# mikrokontroler.net
KiCad netlist of a schematic drawn in Altium Designer
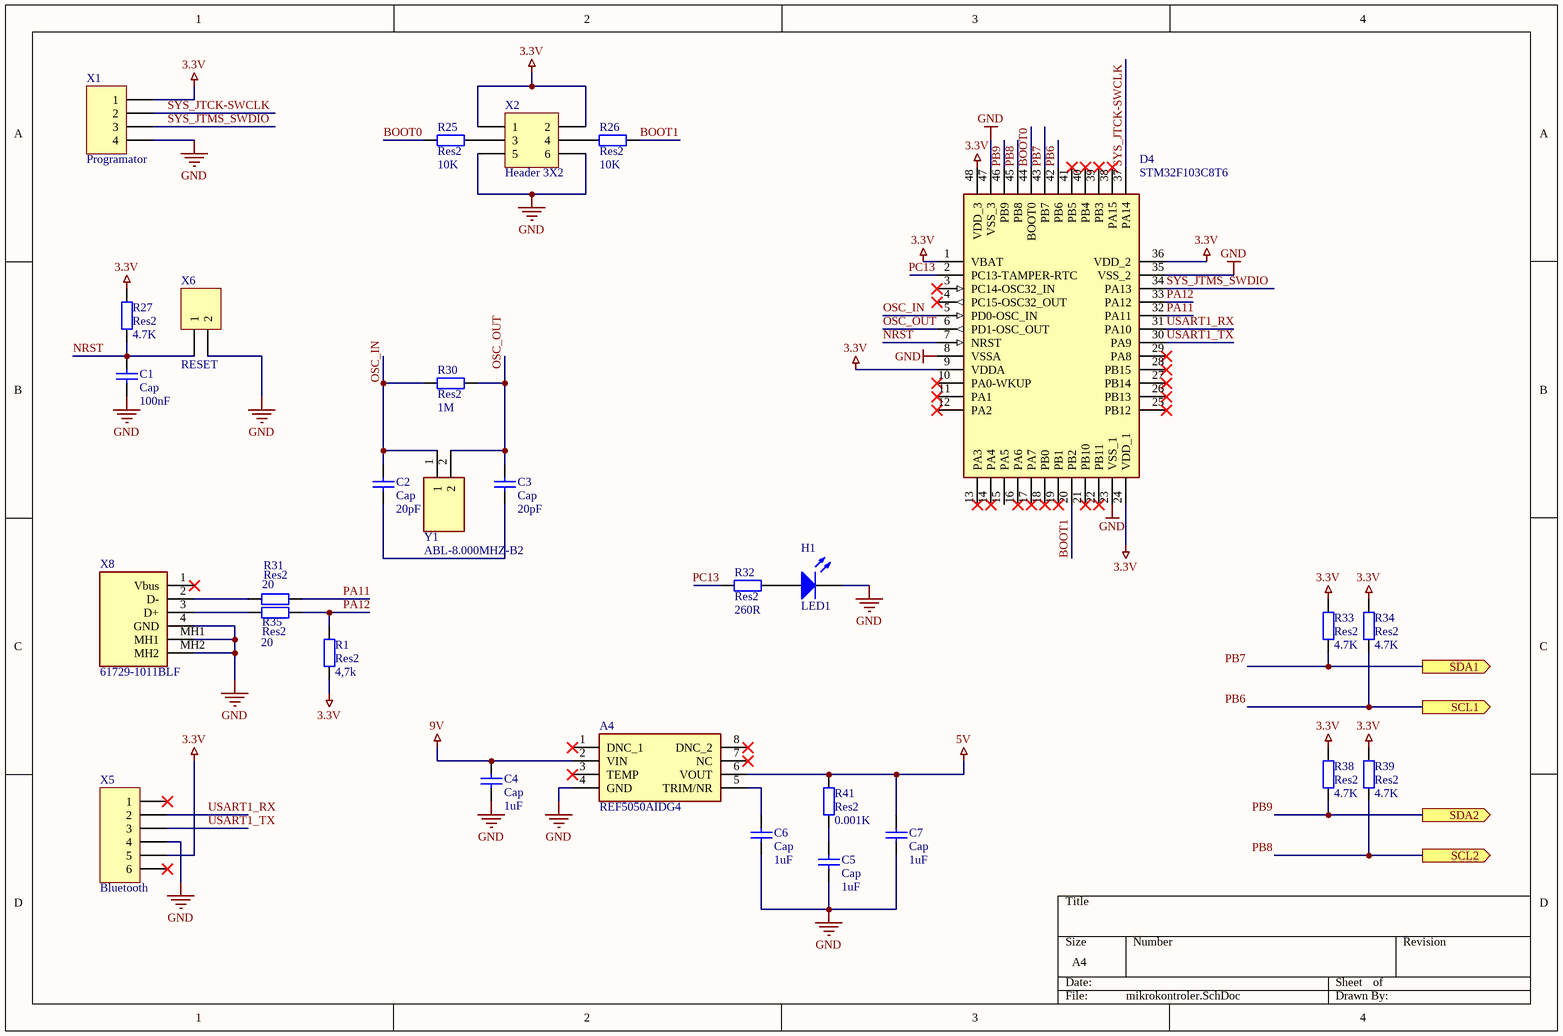
[diagram p0: mikrokontroler.SchDoc]

(export (version "E")
  (design (tool "Eeschema 10.0.6"))
  (components
    (comp (ref "A4")
      (value "REF5050AIDG4")
      (footprint "SamacSys:SOIC127P600X175-8N")
      (description "Integrated Circuit")
      (fields (field (name "MOUSER PART NUMBER") "595-REF5050AIDG4"))
      (libsource (lib "*") (part "REF5050AIDG4"))
    )
    (comp (ref "C1")
      (value "Cap")
      (footprint "6-0805_L")
      (description "Capacitor")
      (fields (field (name "ALTIUM_VALUE") "100nF") (field (name "PUBLISHER") "Altium Limited"))
      (libsource (lib "Miscellaneous Devices") (part "Cap"))
    )
    (comp (ref "C2")
      (value "Cap")
      (footprint "6-0805_L")
      (description "Capacitor")
      (fields (field (name "ALTIUM_VALUE") "20pF") (field (name "PUBLISHER") "Altium Limited"))
      (libsource (lib "Miscellaneous Devices") (part "Cap"))
    )
    (comp (ref "C3")
      (value "Cap")
      (footprint "6-0805_L")
      (description "Capacitor")
      (fields (field (name "ALTIUM_VALUE") "20pF") (field (name "PUBLISHER") "Altium Limited"))
      (libsource (lib "Miscellaneous Devices") (part "Cap"))
    )
    (comp (ref "C4")
      (value "Cap")
      (footprint "6-0805_L")
      (description "Capacitor")
      (fields (field (name "ALTIUM_VALUE") "1uF") (field (name "PUBLISHER") "Altium Limited"))
      (libsource (lib "Miscellaneous Devices") (part "Cap"))
    )
    (comp (ref "C5")
      (value "Cap")
      (footprint "6-0805_L")
      (description "Capacitor")
      (fields (field (name "ALTIUM_VALUE") "1uF") (field (name "PUBLISHER") "Altium Limited"))
      (libsource (lib "Miscellaneous Devices") (part "Cap"))
    )
    (comp (ref "C6")
      (value "Cap")
      (footprint "6-0805_L")
      (description "Capacitor")
      (fields (field (name "ALTIUM_VALUE") "1uF") (field (name "PUBLISHER") "Altium Limited"))
      (libsource (lib "Miscellaneous Devices") (part "Cap"))
    )
    (comp (ref "C7")
      (value "Cap")
      (footprint "6-0805_L")
      (description "Capacitor")
      (fields (field (name "ALTIUM_VALUE") "1uF") (field (name "PUBLISHER") "Altium Limited"))
      (libsource (lib "Miscellaneous Devices") (part "Cap"))
    )
    (comp (ref "D4")
      (value "STM32F103C8T6")
      (footprint "QFP50P900X900X160-48N")
      (description "Integrated Circuit")
      (fields
        (field (name "MOUSER PART NUMBER") "511-STM32F103C8T6")
        (field (name "RS PART NUMBER") "0402279P")
      )
      (libsource (lib "*") (part "STM32F103C8T6"))
    )
    (comp (ref "H1")
      (value "LED1")
      (footprint "LED-1")
      (description "Typical RED GaAs LED")
      (fields (field (name "PUBLISHER") "Altium Limited"))
      (libsource (lib "Miscellaneous Devices") (part "LED1"))
    )
    (comp (ref "R1")
      (value "Res2")
      (footprint "6-0805_L")
      (description "Resistor")
      (fields (field (name "ALTIUM_VALUE") "4,7k") (field (name "PUBLISHER") "Altium Limited"))
      (libsource (lib "") (part "Res2_1"))
    )
    (comp (ref "R25")
      (value "Res2")
      (footprint "6-0805_L")
      (description "Resistor")
      (fields (field (name "ALTIUM_VALUE") "10K") (field (name "PUBLISHER") "Altium Limited"))
      (libsource (lib "") (part "Res2_2"))
    )
    (comp (ref "R26")
      (value "Res2")
      (footprint "6-0805_L")
      (description "Resistor")
      (fields (field (name "ALTIUM_VALUE") "10K") (field (name "PUBLISHER") "Altium Limited"))
      (libsource (lib "") (part "Res2_2"))
    )
    (comp (ref "R27")
      (value "Res2")
      (footprint "6-0805_L")
      (description "Resistor")
      (fields (field (name "ALTIUM_VALUE") "4.7K") (field (name "PUBLISHER") "Altium Limited"))
      (libsource (lib "Miscellaneous Devices") (part "Res2"))
    )
    (comp (ref "R30")
      (value "Res2")
      (footprint "6-0805_L")
      (description "Resistor")
      (fields (field (name "ALTIUM_VALUE") "1M") (field (name "PUBLISHER") "Altium Limited"))
      (libsource (lib "") (part "Res2_2"))
    )
    (comp (ref "R31")
      (value "Res2")
      (footprint "6-0805_L")
      (description "Resistor")
      (fields (field (name "ALTIUM_VALUE") "20") (field (name "PUBLISHER") "Altium Limited"))
      (libsource (lib "") (part "Res2_2"))
    )
    (comp (ref "R32")
      (value "Res2")
      (footprint "6-0805_L")
      (description "Resistor")
      (fields (field (name "ALTIUM_VALUE") "260R") (field (name "PUBLISHER") "Altium Limited"))
      (libsource (lib "") (part "Res2_3"))
    )
    (comp (ref "R33")
      (value "Res2")
      (footprint "6-0805_L")
      (description "Resistor")
      (fields (field (name "ALTIUM_VALUE") "4.7K") (field (name "PUBLISHER") "Altium Limited"))
      (libsource (lib "Miscellaneous Devices") (part "Res2"))
    )
    (comp (ref "R34")
      (value "Res2")
      (footprint "6-0805_L")
      (description "Resistor")
      (fields (field (name "ALTIUM_VALUE") "4.7K") (field (name "PUBLISHER") "Altium Limited"))
      (libsource (lib "Miscellaneous Devices") (part "Res2"))
    )
    (comp (ref "R35")
      (value "Res2")
      (footprint "6-0805_L")
      (description "Resistor")
      (fields (field (name "ALTIUM_VALUE") "20") (field (name "PUBLISHER") "Altium Limited"))
      (libsource (lib "") (part "Res2_2"))
    )
    (comp (ref "R38")
      (value "Res2")
      (footprint "6-0805_L")
      (description "Resistor")
      (fields (field (name "ALTIUM_VALUE") "4.7K") (field (name "PUBLISHER") "Altium Limited"))
      (libsource (lib "Miscellaneous Devices") (part "Res2"))
    )
    (comp (ref "R39")
      (value "Res2")
      (footprint "6-0805_L")
      (description "Resistor")
      (fields (field (name "ALTIUM_VALUE") "4.7K") (field (name "PUBLISHER") "Altium Limited"))
      (libsource (lib "Miscellaneous Devices") (part "Res2"))
    )
    (comp (ref "R41")
      (value "Res2")
      (footprint "6-0805_L")
      (description "Resistor")
      (fields (field (name "ALTIUM_VALUE") "0.001K") (field (name "PUBLISHER") "Altium Limited"))
      (libsource (lib "") (part "Res2_1"))
    )
    (comp (ref "X1")
      (value "Programator")
      (footprint "HDR1X4")
      (description "Header, 4-Pin")
      (fields (field (name "PUBLISHER") "Altium Limited"))
      (libsource (lib "Miscellaneous Connectors") (part "Header 4"))
    )
    (comp (ref "X2")
      (value "Header 3X2")
      (footprint "HDR2X3")
      (description "Header, 3-Pin, Dual row")
      (fields (field (name "PUBLISHER") "Altium Limited"))
      (libsource (lib "Miscellaneous Connectors") (part "Header 3X2"))
    )
    (comp (ref "X5")
      (value "Bluetooth")
      (footprint "HDR1X6")
      (description "Header, 6-Pin")
      (fields (field (name "PUBLISHER") "Altium Limited"))
      (libsource (lib "Miscellaneous Connectors") (part "Header 6"))
    )
    (comp (ref "X6")
      (value "RESET")
      (footprint "HDR1X2")
      (description "Header, 2-Pin")
      (fields (field (name "PUBLISHER") "Altium Limited"))
      (libsource (lib "Miscellaneous Connectors") (part "Header 2"))
    )
    (comp (ref "X8")
      (value "61729-1011BLF")
      (footprint "SamacSys2:617291011BLF")
      (description "Connector")
      (fields
        (field (name "MOUSER PART NUMBER") "649-61729-1011BLF")
        (field (name "RS PART NUMBER") "7710041")
      )
      (libsource (lib "SamacSys2") (part "61729-1011BLF"))
    )
    (comp (ref "Y1")
      (value "ABL-8.000MHZ-B2")
      (footprint "SamacSys2:HC/49US_(AT49)PTH")
      (description "Crystal or Oscillator")
      (fields (field (name "MOUSER PART NUMBER") "815-ABL-8-B2") (field (name "RS PART NUMBER") "1710614"))
      (libsource (lib "*") (part "ABL-8.000MHZ-B2"))
    )
  )
  (nets
    (net (code "1") (name "/BOOT0") (class "Default")
      (node (ref "D4") (pin "44") (pinfunction "BOOT0_44") (pintype "passive"))
      (node (ref "R25") (pin "2") (pinfunction "2_2") (pintype "passive"))
    )
    (net (code "2") (name "/BOOT1") (class "Default")
      (node (ref "D4") (pin "20") (pinfunction "PB2_20") (pintype "passive"))
      (node (ref "R26") (pin "1") (pinfunction "1_1") (pintype "passive"))
    )
    (net (code "3") (name "/NRST") (class "Default")
      (node (ref "C1") (pin "2") (pinfunction "2_2") (pintype "passive"))
      (node (ref "D4") (pin "7") (pinfunction "NRST_7") (pintype "input"))
      (node (ref "R27") (pin "1") (pinfunction "1_1") (pintype "passive"))
      (node (ref "X6") (pin "1") (pinfunction "1_1") (pintype "passive"))
    )
    (net (code "4") (name "/OSC_IN") (class "Default")
      (node (ref "C2") (pin "2") (pinfunction "2_2") (pintype "passive"))
      (node (ref "D4") (pin "5") (pinfunction "PD0-OSC_IN_5") (pintype "input"))
      (node (ref "R30") (pin "2") (pinfunction "2_2") (pintype "passive"))
      (node (ref "Y1") (pin "1") (pinfunction "1_1") (pintype "passive"))
    )
    (net (code "5") (name "/OSC_OUT") (class "Default")
      (node (ref "C3") (pin "2") (pinfunction "2_2") (pintype "passive"))
      (node (ref "D4") (pin "6") (pinfunction "PD1-OSC_OUT_6") (pintype "output"))
      (node (ref "R30") (pin "1") (pinfunction "1_1") (pintype "passive"))
      (node (ref "Y1") (pin "2") (pinfunction "2_2") (pintype "passive"))
    )
    (net (code "6") (name "/PA11") (class "Default")
      (node (ref "D4") (pin "32") (pinfunction "PA11_32") (pintype "passive"))
      (node (ref "R31") (pin "1") (pinfunction "1_1") (pintype "passive"))
    )
    (net (code "7") (name "/PA12") (class "Default")
      (node (ref "D4") (pin "33") (pinfunction "PA12_33") (pintype "passive"))
      (node (ref "R1") (pin "1") (pinfunction "1_1") (pintype "passive"))
      (node (ref "R35") (pin "1") (pinfunction "1_1") (pintype "passive"))
    )
    (net (code "8") (name "/PB6") (class "Default")
      (node (ref "D4") (pin "42") (pinfunction "PB6_42") (pintype "passive"))
      (node (ref "R34") (pin "1") (pinfunction "1_1") (pintype "passive"))
    )
    (net (code "9") (name "/PB7") (class "Default")
      (node (ref "D4") (pin "43") (pinfunction "PB7_43") (pintype "passive"))
      (node (ref "R33") (pin "1") (pinfunction "1_1") (pintype "passive"))
    )
    (net (code "10") (name "/PB8") (class "Default")
      (node (ref "D4") (pin "45") (pinfunction "PB8_45") (pintype "passive"))
      (node (ref "R39") (pin "1") (pinfunction "1_1") (pintype "passive"))
    )
    (net (code "11") (name "/PB9") (class "Default")
      (node (ref "D4") (pin "46") (pinfunction "PB9_46") (pintype "passive"))
      (node (ref "R38") (pin "1") (pinfunction "1_1") (pintype "passive"))
    )
    (net (code "12") (name "/PC13") (class "Default")
      (node (ref "D4") (pin "2") (pinfunction "PC13-TAMPER-RTC_2") (pintype "passive"))
      (node (ref "R32") (pin "1") (pinfunction "1_1") (pintype "passive"))
    )
    (net (code "13") (name "/SYS_JTCK-SWCLK") (class "Default")
      (node (ref "D4") (pin "37") (pinfunction "PA14_37") (pintype "passive"))
      (node (ref "X1") (pin "2") (pinfunction "2_2") (pintype "passive"))
    )
    (net (code "14") (name "/SYS_JTMS_SWDIO") (class "Default")
      (node (ref "D4") (pin "34") (pinfunction "PA13_34") (pintype "passive"))
      (node (ref "X1") (pin "3") (pinfunction "3_3") (pintype "passive"))
    )
    (net (code "15") (name "/USART1_RX") (class "Default")
      (node (ref "D4") (pin "31") (pinfunction "PA10_31") (pintype "passive"))
      (node (ref "X5") (pin "2") (pinfunction "2_2") (pintype "passive"))
    )
    (net (code "16") (name "/USART1_TX") (class "Default")
      (node (ref "D4") (pin "30") (pinfunction "PA9_30") (pintype "passive"))
      (node (ref "X5") (pin "3") (pinfunction "3_3") (pintype "passive"))
    )
    (net (code "17") (name "3.3V") (class "Default")
      (node (ref "D4") (pin "1") (pinfunction "VBAT_1") (pintype "passive"))
      (node (ref "D4") (pin "24") (pinfunction "VDD_1_24") (pintype "power_in"))
      (node (ref "D4") (pin "36") (pinfunction "VDD_2_36") (pintype "power_in"))
      (node (ref "D4") (pin "48") (pinfunction "VDD_3_48") (pintype "power_in"))
      (node (ref "D4") (pin "9") (pinfunction "VDDA_9") (pintype "power_in"))
      (node (ref "R1") (pin "2") (pinfunction "2_2") (pintype "passive"))
      (node (ref "R27") (pin "2") (pinfunction "2_2") (pintype "passive"))
      (node (ref "R33") (pin "2") (pinfunction "2_2") (pintype "passive"))
      (node (ref "R34") (pin "2") (pinfunction "2_2") (pintype "passive"))
      (node (ref "R38") (pin "2") (pinfunction "2_2") (pintype "passive"))
      (node (ref "R39") (pin "2") (pinfunction "2_2") (pintype "passive"))
      (node (ref "X1") (pin "1") (pinfunction "1_1") (pintype "passive"))
      (node (ref "X2") (pin "1") (pinfunction "1_1") (pintype "passive"))
      (node (ref "X2") (pin "2") (pinfunction "2_2") (pintype "passive"))
      (node (ref "X5") (pin "5") (pinfunction "5_5") (pintype "passive"))
    )
    (net (code "18") (name "5V") (class "Default")
      (node (ref "A4") (pin "6") (pinfunction "VOUT_6") (pintype "passive"))
      (node (ref "C7") (pin "2") (pinfunction "2_2") (pintype "passive"))
      (node (ref "R41") (pin "1") (pinfunction "1_1") (pintype "passive"))
    )
    (net (code "19") (name "9V") (class "Default")
      (node (ref "A4") (pin "2") (pinfunction "VIN_2") (pintype "passive"))
      (node (ref "C4") (pin "2") (pinfunction "2_2") (pintype "passive"))
    )
    (net (code "20") (name "GND") (class "Default")
      (node (ref "A4") (pin "4") (pinfunction "GND_4") (pintype "passive"))
      (node (ref "C1") (pin "1") (pinfunction "1_1") (pintype "passive"))
      (node (ref "C4") (pin "1") (pinfunction "1_1") (pintype "passive"))
      (node (ref "C5") (pin "1") (pinfunction "1_1") (pintype "passive"))
      (node (ref "C6") (pin "1") (pinfunction "1_1") (pintype "passive"))
      (node (ref "C7") (pin "1") (pinfunction "1_1") (pintype "passive"))
      (node (ref "D4") (pin "23") (pinfunction "VSS_1_23") (pintype "power_in"))
      (node (ref "D4") (pin "35") (pinfunction "VSS_2_35") (pintype "power_in"))
      (node (ref "D4") (pin "47") (pinfunction "VSS_3_47") (pintype "power_in"))
      (node (ref "D4") (pin "8") (pinfunction "VSSA_8") (pintype "power_in"))
      (node (ref "H1") (pin "2") (pinfunction "K_2") (pintype "passive"))
      (node (ref "X1") (pin "4") (pinfunction "4_4") (pintype "passive"))
      (node (ref "X2") (pin "5") (pinfunction "5_5") (pintype "passive"))
      (node (ref "X2") (pin "6") (pinfunction "6_6") (pintype "passive"))
      (node (ref "X5") (pin "4") (pinfunction "4_4") (pintype "passive"))
      (node (ref "X6") (pin "2") (pinfunction "2_2") (pintype "passive"))
      (node (ref "X8") (pin "4") (pinfunction "GND_4") (pintype "passive"))
      (node (ref "X8") (pin "MH1") (pinfunction "MH1_MH1") (pintype "passive"))
      (node (ref "X8") (pin "MH2") (pinfunction "MH2_MH2") (pintype "passive"))
    )
    (net (code "21") (name "Net-(A4-TRIM{slash}NR)") (class "Default")
      (node (ref "A4") (pin "5") (pinfunction "TRIM/NR_5") (pintype "passive"))
      (node (ref "C6") (pin "2") (pinfunction "2_2") (pintype "passive"))
    )
    (net (code "22") (name "Net-(C2-Pad1)") (class "Default")
      (node (ref "C2") (pin "1") (pinfunction "1_1") (pintype "passive"))
      (node (ref "C3") (pin "1") (pinfunction "1_1") (pintype "passive"))
    )
    (net (code "23") (name "Net-(C5-Pad2)") (class "Default")
      (node (ref "C5") (pin "2") (pinfunction "2_2") (pintype "passive"))
      (node (ref "R41") (pin "2") (pinfunction "2_2") (pintype "passive"))
    )
    (net (code "24") (name "Net-(H1-A)") (class "Default")
      (node (ref "H1") (pin "1") (pinfunction "A_1") (pintype "passive"))
      (node (ref "R32") (pin "2") (pinfunction "2_2") (pintype "passive"))
    )
    (net (code "25") (name "Net-(R25-Pad1)") (class "Default")
      (node (ref "R25") (pin "1") (pinfunction "1_1") (pintype "passive"))
      (node (ref "X2") (pin "3") (pinfunction "3_3") (pintype "passive"))
    )
    (net (code "26") (name "Net-(R26-Pad2)") (class "Default")
      (node (ref "R26") (pin "2") (pinfunction "2_2") (pintype "passive"))
      (node (ref "X2") (pin "4") (pinfunction "4_4") (pintype "passive"))
    )
    (net (code "27") (name "Net-(X8-D+)") (class "Default")
      (node (ref "R35") (pin "2") (pinfunction "2_2") (pintype "passive"))
      (node (ref "X8") (pin "3") (pinfunction "D+_3") (pintype "passive"))
    )
    (net (code "28") (name "Net-(X8-D-)") (class "Default")
      (node (ref "R31") (pin "2") (pinfunction "2_2") (pintype "passive"))
      (node (ref "X8") (pin "2") (pinfunction "D-_2") (pintype "passive"))
    )
    (net (code "29") (name "unconnected-(A4-DNC_1-Pad1)") (class "Default")
      (node (ref "A4") (pin "1") (pinfunction "DNC_1_1") (pintype "passive+no_connect"))
    )
    (net (code "30") (name "unconnected-(A4-DNC_2-Pad8)") (class "Default")
      (node (ref "A4") (pin "8") (pinfunction "DNC_2_8") (pintype "passive+no_connect"))
    )
    (net (code "31") (name "unconnected-(A4-NC-Pad7)") (class "Default")
      (node (ref "A4") (pin "7") (pinfunction "NC_7") (pintype "passive+no_connect"))
    )
    (net (code "32") (name "unconnected-(A4-TEMP-Pad3)") (class "Default")
      (node (ref "A4") (pin "3") (pinfunction "TEMP_3") (pintype "passive+no_connect"))
    )
    (net (code "33") (name "unconnected-(D4-PA0-WKUP-Pad10)") (class "Default")
      (node (ref "D4") (pin "10") (pinfunction "PA0-WKUP_10") (pintype "passive+no_connect"))
    )
    (net (code "34") (name "unconnected-(D4-PA1-Pad11)") (class "Default")
      (node (ref "D4") (pin "11") (pinfunction "PA1_11") (pintype "passive+no_connect"))
    )
    (net (code "35") (name "unconnected-(D4-PA2-Pad12)") (class "Default")
      (node (ref "D4") (pin "12") (pinfunction "PA2_12") (pintype "passive+no_connect"))
    )
    (net (code "36") (name "unconnected-(D4-PA3-Pad13)") (class "Default")
      (node (ref "D4") (pin "13") (pinfunction "PA3_13") (pintype "passive+no_connect"))
    )
    (net (code "37") (name "unconnected-(D4-PA4-Pad14)") (class "Default")
      (node (ref "D4") (pin "14") (pinfunction "PA4_14") (pintype "passive+no_connect"))
    )
    (net (code "38") (name "unconnected-(D4-PA5-Pad15)") (class "Default")
      (node (ref "D4") (pin "15") (pinfunction "PA5_15") (pintype "passive"))
    )
    (net (code "39") (name "unconnected-(D4-PA6-Pad16)") (class "Default")
      (node (ref "D4") (pin "16") (pinfunction "PA6_16") (pintype "passive+no_connect"))
    )
    (net (code "40") (name "unconnected-(D4-PA7-Pad17)") (class "Default")
      (node (ref "D4") (pin "17") (pinfunction "PA7_17") (pintype "passive+no_connect"))
    )
    (net (code "41") (name "unconnected-(D4-PA8-Pad29)") (class "Default")
      (node (ref "D4") (pin "29") (pinfunction "PA8_29") (pintype "passive+no_connect"))
    )
    (net (code "42") (name "unconnected-(D4-PA15-Pad38)") (class "Default")
      (node (ref "D4") (pin "38") (pinfunction "PA15_38") (pintype "passive+no_connect"))
    )
    (net (code "43") (name "unconnected-(D4-PB0-Pad18)") (class "Default")
      (node (ref "D4") (pin "18") (pinfunction "PB0_18") (pintype "passive+no_connect"))
    )
    (net (code "44") (name "unconnected-(D4-PB1-Pad19)") (class "Default")
      (node (ref "D4") (pin "19") (pinfunction "PB1_19") (pintype "passive+no_connect"))
    )
    (net (code "45") (name "unconnected-(D4-PB3-Pad39)") (class "Default")
      (node (ref "D4") (pin "39") (pinfunction "PB3_39") (pintype "passive+no_connect"))
    )
    (net (code "46") (name "unconnected-(D4-PB4-Pad40)") (class "Default")
      (node (ref "D4") (pin "40") (pinfunction "PB4_40") (pintype "passive+no_connect"))
    )
    (net (code "47") (name "unconnected-(D4-PB5-Pad41)") (class "Default")
      (node (ref "D4") (pin "41") (pinfunction "PB5_41") (pintype "passive+no_connect"))
    )
    (net (code "48") (name "unconnected-(D4-PB10-Pad21)") (class "Default")
      (node (ref "D4") (pin "21") (pinfunction "PB10_21") (pintype "passive+no_connect"))
    )
    (net (code "49") (name "unconnected-(D4-PB11-Pad22)") (class "Default")
      (node (ref "D4") (pin "22") (pinfunction "PB11_22") (pintype "passive+no_connect"))
    )
    (net (code "50") (name "unconnected-(D4-PB12-Pad25)") (class "Default")
      (node (ref "D4") (pin "25") (pinfunction "PB12_25") (pintype "passive+no_connect"))
    )
    (net (code "51") (name "unconnected-(D4-PB13-Pad26)") (class "Default")
      (node (ref "D4") (pin "26") (pinfunction "PB13_26") (pintype "passive+no_connect"))
    )
    (net (code "52") (name "unconnected-(D4-PB14-Pad27)") (class "Default")
      (node (ref "D4") (pin "27") (pinfunction "PB14_27") (pintype "passive+no_connect"))
    )
    (net (code "53") (name "unconnected-(D4-PB15-Pad28)") (class "Default")
      (node (ref "D4") (pin "28") (pinfunction "PB15_28") (pintype "passive+no_connect"))
    )
    (net (code "54") (name "unconnected-(D4-PC14-OSC32_IN-Pad3)") (class "Default")
      (node (ref "D4") (pin "3") (pinfunction "PC14-OSC32_IN_3") (pintype "input+no_connect"))
    )
    (net (code "55") (name "unconnected-(D4-PC15-OSC32_OUT-Pad4)") (class "Default")
      (node (ref "D4") (pin "4") (pinfunction "PC15-OSC32_OUT_4") (pintype "output+no_connect"))
    )
    (net (code "56") (name "unconnected-(X5-Pad1)") (class "Default")
      (node (ref "X5") (pin "1") (pinfunction "1_1") (pintype "passive+no_connect"))
    )
    (net (code "57") (name "unconnected-(X5-Pad6)") (class "Default")
      (node (ref "X5") (pin "6") (pinfunction "6_6") (pintype "passive+no_connect"))
    )
    (net (code "58") (name "unconnected-(X8-Vbus-Pad1)") (class "Default")
      (node (ref "X8") (pin "1") (pinfunction "Vbus_1") (pintype "passive+no_connect"))
    )
  )
)
